# PSoC_DCO_Mini_Shield.net
KiCad netlist of a schematic drawn in EAGLE
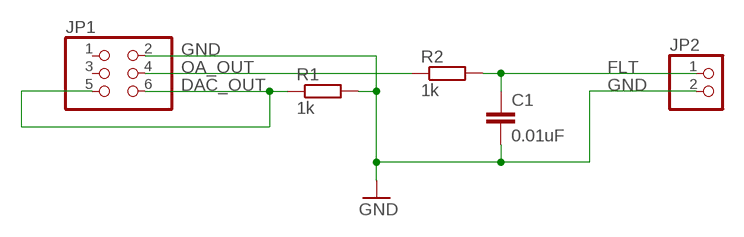
[diagram p0: schematic, sheet 1]

(export (version "E")
  (design (tool "Eeschema 10.0.6"))
  (components
    (comp (ref "C1")
      (value "0.01uF")
      (footprint "eagle-import:C025-025X050")
      (libsource (lib "eagle-import") (part "C-EU025-025X050"))
    )
    (comp (ref "JP1")
      (value "PINHD-2X3")
      (footprint "eagle-import:2X03")
      (libsource (lib "eagle-import") (part "PINHD-2X3"))
    )
    (comp (ref "JP2")
      (value "PINHD-1X2")
      (footprint "eagle-import:1X02")
      (libsource (lib "eagle-import") (part "PINHD-1X2"))
    )
    (comp (ref "R1")
      (value "1k")
      (footprint "eagle-import:0207_7")
      (libsource (lib "eagle-import") (part "R-EU_0207/7"))
    )
    (comp (ref "R2")
      (value "1k")
      (footprint "eagle-import:0207_7")
      (libsource (lib "eagle-import") (part "R-EU_0207/7"))
    )
  )
  (nets
    (net (code "1") (name "/DAC_OUT") (class "Default")
      (node (ref "JP1") (pin "5") (pinfunction "5_5") (pintype "passive"))
      (node (ref "JP1") (pin "6") (pinfunction "6_6") (pintype "passive"))
      (node (ref "R1") (pin "1") (pinfunction "1_1") (pintype "passive"))
    )
    (net (code "2") (name "/FLT") (class "Default")
      (node (ref "C1") (pin "1") (pinfunction "1_1") (pintype "passive"))
      (node (ref "JP2") (pin "1") (pinfunction "1_1") (pintype "passive"))
      (node (ref "R2") (pin "2") (pinfunction "2_2") (pintype "passive"))
    )
    (net (code "3") (name "/OA_OUT") (class "Default")
      (node (ref "JP1") (pin "4") (pinfunction "4_4") (pintype "passive"))
      (node (ref "R2") (pin "1") (pinfunction "1_1") (pintype "passive"))
    )
    (net (code "4") (name "GND") (class "Default")
      (node (ref "C1") (pin "2") (pinfunction "2_2") (pintype "passive"))
      (node (ref "JP1") (pin "2") (pinfunction "2_2") (pintype "passive"))
      (node (ref "JP2") (pin "2") (pinfunction "2_2") (pintype "passive"))
      (node (ref "R1") (pin "2") (pinfunction "2_2") (pintype "passive"))
    )
    (net (code "5") (name "unconnected-(JP1-Pad1)") (class "Default")
      (node (ref "JP1") (pin "1") (pinfunction "1_1") (pintype "passive"))
    )
    (net (code "6") (name "unconnected-(JP1-Pad3)") (class "Default")
      (node (ref "JP1") (pin "3") (pinfunction "3_3") (pintype "passive"))
    )
  )
)
